# Rpi_Shield_V1_2.net
KiCad netlist of a schematic drawn in EAGLE
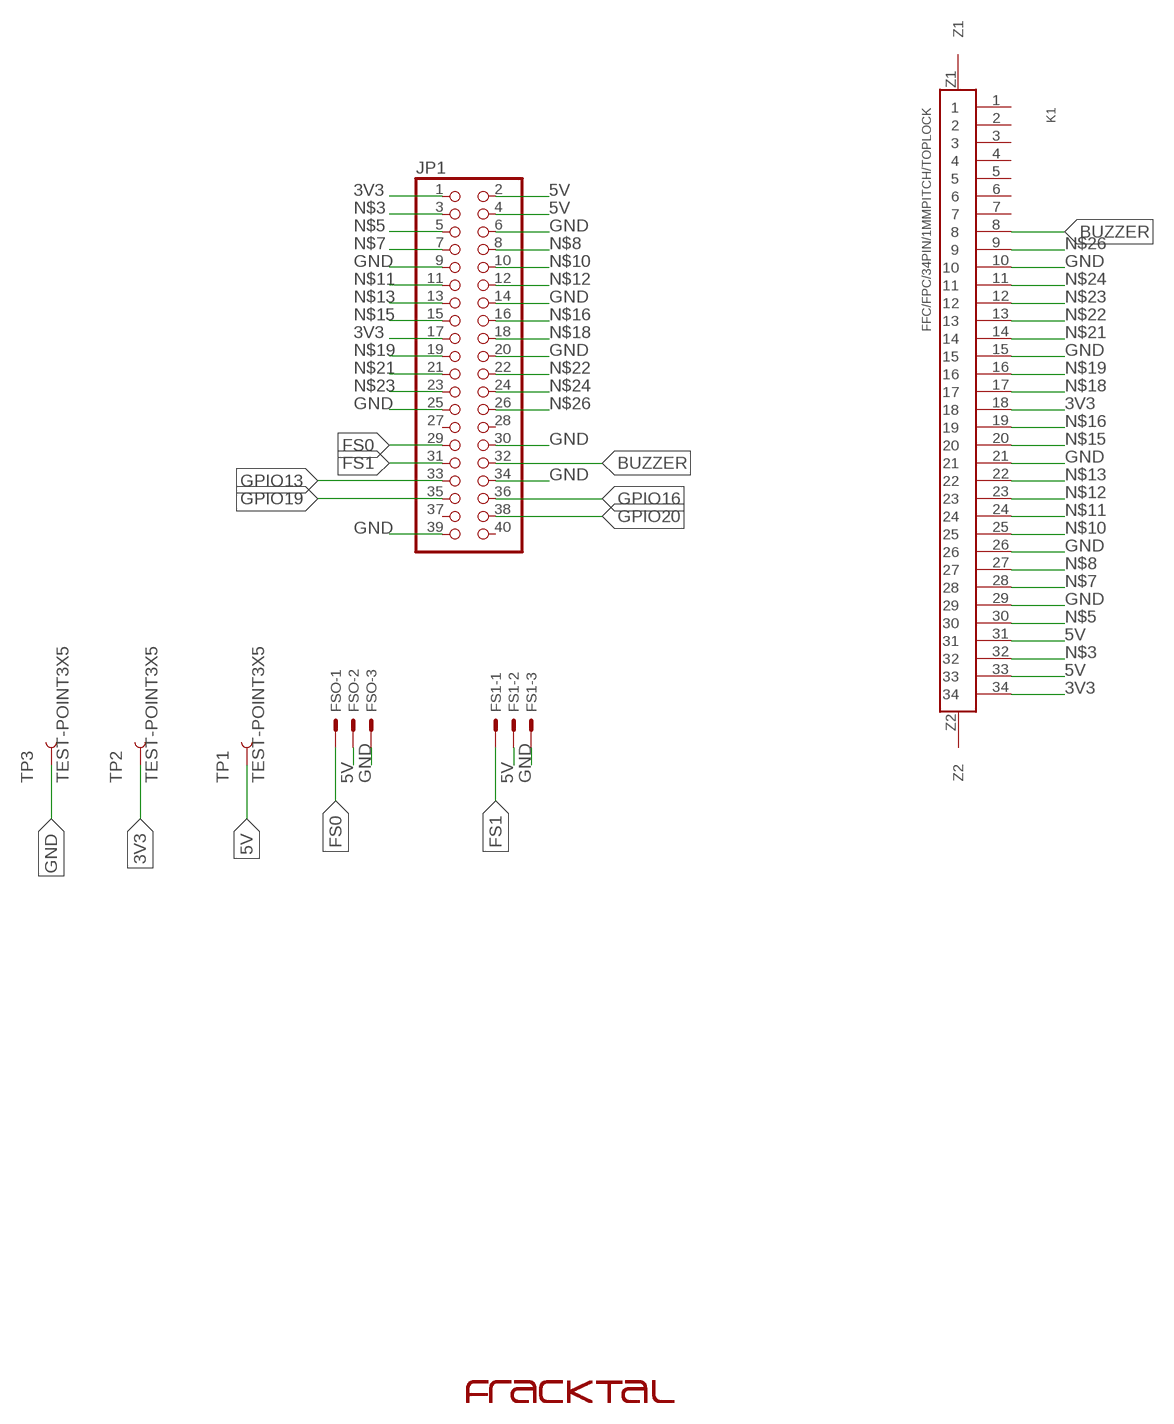
[diagram p0: schematic, sheet 1]

(export (version "E")
  (design (tool "Eeschema 10.0.6"))
  (components
    (comp (ref "FS1")
      (value "JST-XH-03-PIN-LONG-PAD")
      (footprint "eagle-import:JST-XH-03-PACKAGE-LONG-PAD")
      (libsource (lib "eagle-import") (part "JST-XH-03-PIN-LONG-PAD"))
    )
    (comp (ref "FSO")
      (value "JST-XH-03-PIN-LONG-PAD")
      (footprint "eagle-import:JST-XH-03-PACKAGE-LONG-PAD")
      (libsource (lib "eagle-import") (part "JST-XH-03-PIN-LONG-PAD"))
    )
    (comp (ref "JP1")
      (value "RASPBERRYPI_3B_GPIO")
      (footprint "eagle-import:RASPBERRYPI_3B_GPIO")
      (libsource (lib "eagle-import") (part "RASPBERRYPI_3B_GPIO"))
    )
    (comp (ref "K1")
      (value "FFC/FPC/34PIN/1MMPITCH/TOPLOCK")
      (footprint "eagle-import:FFC_FPC_34PIN_1MMPITCH_TOPLOCK")
      (libsource (lib "eagle-import") (part "FFC/FPC/34PIN/1MMPITCH/TOPLOCK"))
    )
    (comp (ref "TP1")
      (value "TEST-POINT3X5")
      (footprint "eagle-import:PAD.03X.05")
      (libsource (lib "eagle-import") (part "TEST-POINT3X5"))
    )
    (comp (ref "TP2")
      (value "TEST-POINT3X5")
      (footprint "eagle-import:PAD.03X.05")
      (libsource (lib "eagle-import") (part "TEST-POINT3X5"))
    )
    (comp (ref "TP3")
      (value "TEST-POINT3X5")
      (footprint "eagle-import:PAD.03X.05")
      (libsource (lib "eagle-import") (part "TEST-POINT3X5"))
    )
    (comp (ref "U$1")
      (value "FRACKTALLOGO")
      (footprint "eagle-import:FRACKTALLOGO")
      (libsource (lib "eagle-import") (part "FRACKTALLOGO"))
    )
  )
  (nets
    (net (code "1") (name "/N$3") (class "Default")
      (node (ref "JP1") (pin "3") (pinfunction "3_3") (pintype "passive"))
      (node (ref "K1") (pin "32") (pinfunction "32_32") (pintype "bidirectional"))
    )
    (net (code "2") (name "/N$5") (class "Default")
      (node (ref "JP1") (pin "5") (pinfunction "5_5") (pintype "passive"))
      (node (ref "K1") (pin "30") (pinfunction "30_30") (pintype "bidirectional"))
    )
    (net (code "3") (name "/N$7") (class "Default")
      (node (ref "JP1") (pin "7") (pinfunction "7_7") (pintype "passive"))
      (node (ref "K1") (pin "28") (pinfunction "28_28") (pintype "bidirectional"))
    )
    (net (code "4") (name "/N$8") (class "Default")
      (node (ref "JP1") (pin "8") (pinfunction "8_8") (pintype "passive"))
      (node (ref "K1") (pin "27") (pinfunction "27_27") (pintype "bidirectional"))
    )
    (net (code "5") (name "/N$10") (class "Default")
      (node (ref "JP1") (pin "10") (pinfunction "10_10") (pintype "passive"))
      (node (ref "K1") (pin "25") (pinfunction "25_25") (pintype "bidirectional"))
    )
    (net (code "6") (name "/N$11") (class "Default")
      (node (ref "JP1") (pin "11") (pinfunction "11_11") (pintype "passive"))
      (node (ref "K1") (pin "24") (pinfunction "24_24") (pintype "bidirectional"))
    )
    (net (code "7") (name "/N$12") (class "Default")
      (node (ref "JP1") (pin "12") (pinfunction "12_12") (pintype "passive"))
      (node (ref "K1") (pin "23") (pinfunction "23_23") (pintype "bidirectional"))
    )
    (net (code "8") (name "/N$13") (class "Default")
      (node (ref "JP1") (pin "13") (pinfunction "13_13") (pintype "passive"))
      (node (ref "K1") (pin "22") (pinfunction "22_22") (pintype "bidirectional"))
    )
    (net (code "9") (name "/N$15") (class "Default")
      (node (ref "JP1") (pin "15") (pinfunction "15_15") (pintype "passive"))
      (node (ref "K1") (pin "20") (pinfunction "20_20") (pintype "bidirectional"))
    )
    (net (code "10") (name "/N$16") (class "Default")
      (node (ref "JP1") (pin "16") (pinfunction "16_16") (pintype "passive"))
      (node (ref "K1") (pin "19") (pinfunction "19_19") (pintype "bidirectional"))
    )
    (net (code "11") (name "/N$18") (class "Default")
      (node (ref "JP1") (pin "18") (pinfunction "18_18") (pintype "passive"))
      (node (ref "K1") (pin "17") (pinfunction "17_17") (pintype "bidirectional"))
    )
    (net (code "12") (name "/N$19") (class "Default")
      (node (ref "JP1") (pin "19") (pinfunction "19_19") (pintype "passive"))
      (node (ref "K1") (pin "16") (pinfunction "16_16") (pintype "bidirectional"))
    )
    (net (code "13") (name "/N$21") (class "Default")
      (node (ref "JP1") (pin "21") (pinfunction "21_21") (pintype "passive"))
      (node (ref "K1") (pin "14") (pinfunction "14_14") (pintype "bidirectional"))
    )
    (net (code "14") (name "/N$22") (class "Default")
      (node (ref "JP1") (pin "22") (pinfunction "22_22") (pintype "passive"))
      (node (ref "K1") (pin "13") (pinfunction "13_13") (pintype "bidirectional"))
    )
    (net (code "15") (name "/N$23") (class "Default")
      (node (ref "JP1") (pin "23") (pinfunction "23_23") (pintype "passive"))
      (node (ref "K1") (pin "12") (pinfunction "12_12") (pintype "bidirectional"))
    )
    (net (code "16") (name "/N$24") (class "Default")
      (node (ref "JP1") (pin "24") (pinfunction "24_24") (pintype "passive"))
      (node (ref "K1") (pin "11") (pinfunction "11_11") (pintype "bidirectional"))
    )
    (net (code "17") (name "/N$26") (class "Default")
      (node (ref "JP1") (pin "26") (pinfunction "26_26") (pintype "passive"))
      (node (ref "K1") (pin "9") (pinfunction "9_9") (pintype "bidirectional"))
    )
    (net (code "18") (name "3V3") (class "Default")
      (node (ref "JP1") (pin "1") (pinfunction "1_1") (pintype "passive"))
      (node (ref "JP1") (pin "17") (pinfunction "17_17") (pintype "passive"))
      (node (ref "K1") (pin "18") (pinfunction "18_18") (pintype "bidirectional"))
      (node (ref "K1") (pin "34") (pinfunction "34_34") (pintype "bidirectional"))
      (node (ref "TP2") (pin "P$1") (pinfunction "1_P$1") (pintype "bidirectional"))
    )
    (net (code "19") (name "5V") (class "Default")
      (node (ref "FS1") (pin "2") (pinfunction "S_2") (pintype "passive"))
      (node (ref "FSO") (pin "2") (pinfunction "S_2") (pintype "passive"))
      (node (ref "JP1") (pin "2") (pinfunction "2_2") (pintype "passive"))
      (node (ref "JP1") (pin "4") (pinfunction "4_4") (pintype "passive"))
      (node (ref "K1") (pin "31") (pinfunction "31_31") (pintype "bidirectional"))
      (node (ref "K1") (pin "33") (pinfunction "33_33") (pintype "bidirectional"))
      (node (ref "TP1") (pin "P$1") (pinfunction "1_P$1") (pintype "bidirectional"))
    )
    (net (code "20") (name "BUZZER") (class "Default")
      (node (ref "JP1") (pin "32") (pinfunction "32_32") (pintype "passive"))
      (node (ref "K1") (pin "8") (pinfunction "8_8") (pintype "bidirectional"))
    )
    (net (code "21") (name "FS0") (class "Default")
      (node (ref "FSO") (pin "1") (pinfunction "S_1") (pintype "passive"))
      (node (ref "JP1") (pin "29") (pinfunction "29_29") (pintype "passive"))
    )
    (net (code "22") (name "FS1") (class "Default")
      (node (ref "FS1") (pin "1") (pinfunction "S_1") (pintype "passive"))
      (node (ref "JP1") (pin "31") (pinfunction "31_31") (pintype "passive"))
    )
    (net (code "23") (name "GND") (class "Default")
      (node (ref "FS1") (pin "3") (pinfunction "S_3") (pintype "passive"))
      (node (ref "FSO") (pin "3") (pinfunction "S_3") (pintype "passive"))
      (node (ref "JP1") (pin "14") (pinfunction "14_14") (pintype "passive"))
      (node (ref "JP1") (pin "20") (pinfunction "20_20") (pintype "passive"))
      (node (ref "JP1") (pin "25") (pinfunction "25_25") (pintype "passive"))
      (node (ref "JP1") (pin "30") (pinfunction "30_30") (pintype "passive"))
      (node (ref "JP1") (pin "34") (pinfunction "34_34") (pintype "passive"))
      (node (ref "JP1") (pin "39") (pinfunction "39_39") (pintype "passive"))
      (node (ref "JP1") (pin "6") (pinfunction "6_6") (pintype "passive"))
      (node (ref "JP1") (pin "9") (pinfunction "9_9") (pintype "passive"))
      (node (ref "K1") (pin "10") (pinfunction "10_10") (pintype "bidirectional"))
      (node (ref "K1") (pin "15") (pinfunction "15_15") (pintype "bidirectional"))
      (node (ref "K1") (pin "21") (pinfunction "21_21") (pintype "bidirectional"))
      (node (ref "K1") (pin "26") (pinfunction "26_26") (pintype "bidirectional"))
      (node (ref "K1") (pin "29") (pinfunction "29_29") (pintype "bidirectional"))
      (node (ref "TP3") (pin "P$1") (pinfunction "1_P$1") (pintype "bidirectional"))
    )
    (net (code "24") (name "GPIO13") (class "Default")
      (node (ref "JP1") (pin "33") (pinfunction "33_33") (pintype "passive"))
    )
    (net (code "25") (name "GPIO16") (class "Default")
      (node (ref "JP1") (pin "36") (pinfunction "36_36") (pintype "passive"))
    )
    (net (code "26") (name "GPIO19") (class "Default")
      (node (ref "JP1") (pin "35") (pinfunction "35_35") (pintype "passive"))
    )
    (net (code "27") (name "GPIO20") (class "Default")
      (node (ref "JP1") (pin "38") (pinfunction "38_38") (pintype "passive"))
    )
    (net (code "28") (name "unconnected-(JP1-Pad27)") (class "Default")
      (node (ref "JP1") (pin "27") (pinfunction "27_27") (pintype "passive"))
    )
    (net (code "29") (name "unconnected-(JP1-Pad28)") (class "Default")
      (node (ref "JP1") (pin "28") (pinfunction "28_28") (pintype "passive"))
    )
    (net (code "30") (name "unconnected-(JP1-Pad37)") (class "Default")
      (node (ref "JP1") (pin "37") (pinfunction "37_37") (pintype "passive"))
    )
    (net (code "31") (name "unconnected-(JP1-Pad40)") (class "Default")
      (node (ref "JP1") (pin "40") (pinfunction "40_40") (pintype "passive"))
    )
    (net (code "32") (name "unconnected-(K1-Pad1)") (class "Default")
      (node (ref "K1") (pin "1") (pinfunction "1_1") (pintype "bidirectional"))
    )
    (net (code "33") (name "unconnected-(K1-Pad2)") (class "Default")
      (node (ref "K1") (pin "2") (pinfunction "2_2") (pintype "bidirectional"))
    )
    (net (code "34") (name "unconnected-(K1-Pad3)") (class "Default")
      (node (ref "K1") (pin "3") (pinfunction "3_3") (pintype "bidirectional"))
    )
    (net (code "35") (name "unconnected-(K1-Pad4)") (class "Default")
      (node (ref "K1") (pin "4") (pinfunction "4_4") (pintype "bidirectional"))
    )
    (net (code "36") (name "unconnected-(K1-Pad5)") (class "Default")
      (node (ref "K1") (pin "5") (pinfunction "5_5") (pintype "bidirectional"))
    )
    (net (code "37") (name "unconnected-(K1-Pad6)") (class "Default")
      (node (ref "K1") (pin "6") (pinfunction "6_6") (pintype "bidirectional"))
    )
    (net (code "38") (name "unconnected-(K1-Pad7)") (class "Default")
      (node (ref "K1") (pin "7") (pinfunction "7_7") (pintype "bidirectional"))
    )
    (net (code "39") (name "unconnected-(K1-PadZ1)") (class "Default")
      (node (ref "K1") (pin "Z1") (pinfunction "Z1_Z1") (pintype "bidirectional"))
    )
    (net (code "40") (name "unconnected-(K1-PadZ2)") (class "Default")
      (node (ref "K1") (pin "Z2") (pinfunction "Z2_Z2") (pintype "bidirectional"))
    )
  )
)
